# STM32_IO.net
KiCad netlist of a schematic drawn in Altium Designer
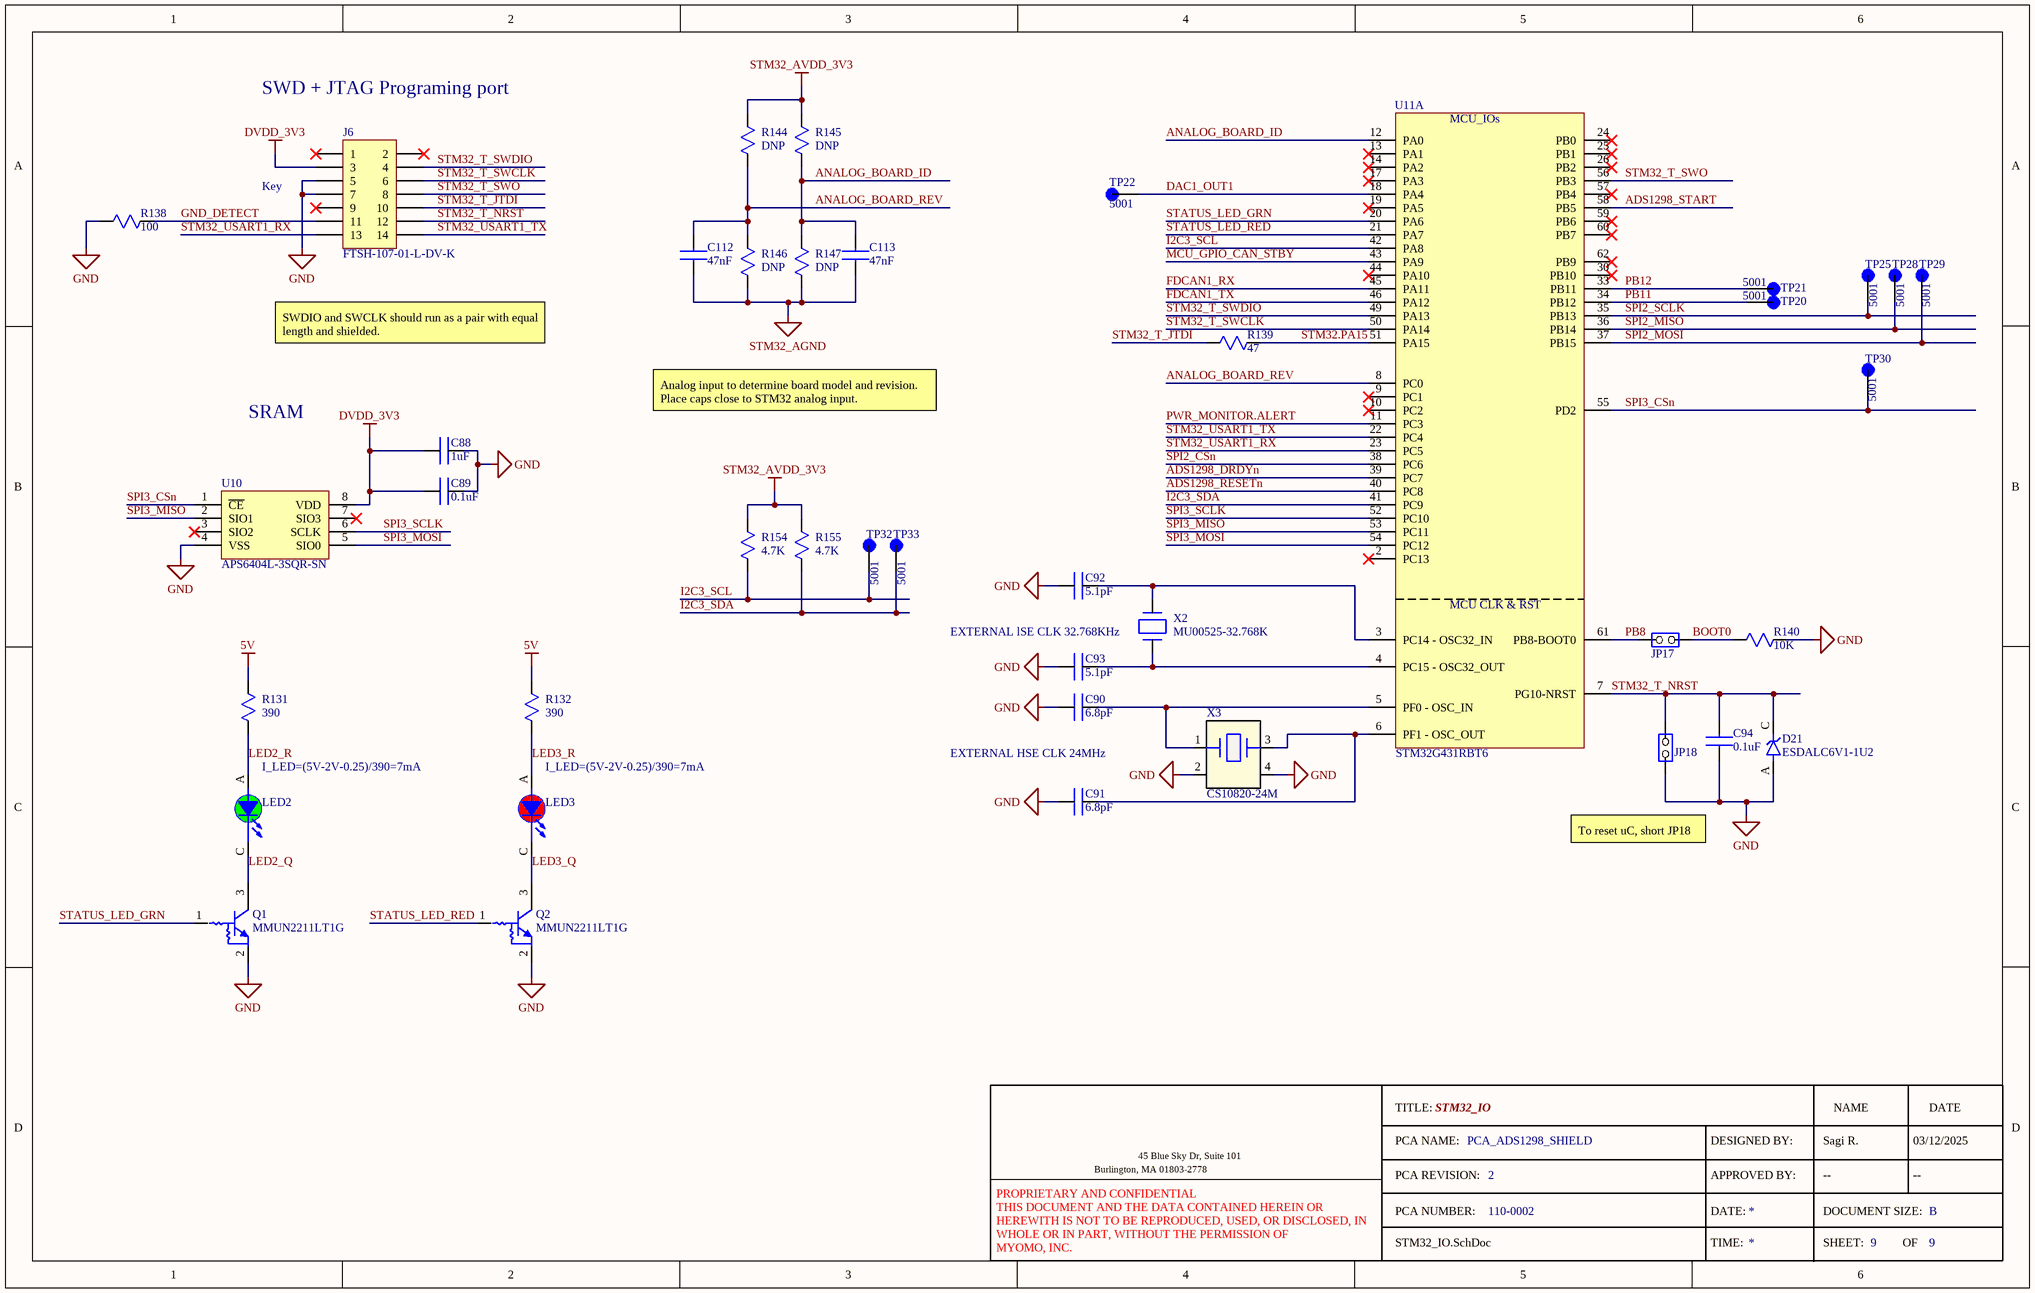
[diagram p0: STM32_IO.SchDoc]

(export (version "E")
  (design (tool "Eeschema 10.0.6"))
  (components
    (comp (ref "C88")
      (value "1uF")
      (footprint "0603")
      (description "CAP CER 1UF 50V X7R 0603")
      (fields (field (name "MFG") "YAGEO"))
      (libsource (lib "Myomo_SCH_Library") (part "C_0603_CER_1uF_50V_X7R"))
    )
    (comp (ref "C89")
      (value "0.1uF")
      (footprint "0402")
      (description "CAP CER 0.1UF 50V X7R 0402")
      (fields (field (name "MFG") "Samsung"))
      (libsource (lib "") (part "C_0402_CER_0.1uF_50V_X7R_1"))
    )
    (comp (ref "C90")
      (value "6.8pF")
      (footprint "0402")
      (description "CAP CER 6.8PF 50V C0G/NPO 0402")
      (fields (field (name "MFG") "YAGEO"))
      (libsource (lib "Myomo_SCH_Library") (part "C_0402_CER_6.8pF_50V_COG"))
    )
    (comp (ref "C91")
      (value "6.8pF")
      (footprint "0402")
      (description "CAP CER 6.8PF 50V C0G/NPO 0402")
      (fields (field (name "MFG") "YAGEO"))
      (libsource (lib "Myomo_SCH_Library") (part "C_0402_CER_6.8pF_50V_COG"))
    )
    (comp (ref "C92")
      (value "5.1pF")
      (footprint "0402")
      (description "CAP CER 5.1PF 50V C0G/NPO 0402")
      (fields (field (name "MFG") "YAGEO"))
      (libsource (lib "Myomo_SCH_Library") (part "C_0402_CER_5.1pF_50V_COG"))
    )
    (comp (ref "C93")
      (value "5.1pF")
      (footprint "0402")
      (description "CAP CER 5.1PF 50V C0G/NPO 0402")
      (fields (field (name "MFG") "YAGEO"))
      (libsource (lib "Myomo_SCH_Library") (part "C_0402_CER_5.1pF_50V_COG"))
    )
    (comp (ref "C94")
      (value "0.1uF")
      (footprint "0402")
      (description "CAP CER 0.1UF 50V X7R 0402")
      (fields (field (name "MFG") "Samsung"))
      (libsource (lib "Myomo_SCH_Library") (part "C_0402_CER_0.1uF_50V_X7R"))
    )
    (comp (ref "C112")
      (value "47nF")
      (footprint "0402")
      (description "CAP CER 47nF 50V X7R 0402")
      (fields (field (name "MFG") "TDK"))
      (libsource (lib "Myomo_SCH_Library") (part "C_0402_CER_47nF_50V_X7R"))
    )
    (comp (ref "C113")
      (value "47nF")
      (footprint "0402")
      (description "CAP CER 47nF 50V X7R 0402")
      (fields (field (name "MFG") "TDK"))
      (libsource (lib "Myomo_SCH_Library") (part "C_0402_CER_47nF_50V_X7R"))
    )
    (comp (ref "D21")
      (value "ESDALC6V1-1U2")
      (footprint "D_TVS_6.1V_20W")
      (description "TVS DIODE 3VRS ST 0201")
      (fields (field (name "MFG") "STMicroelectronics"))
      (libsource (lib "Myomo_SCH_Library") (part "D_TVS_6.1V_20W"))
    )
    (comp (ref "J6")
      (value "FTSH-107-01-L-DV-K")
      (footprint "J_SAMTEC_FTSH-107-01-L-DV-K")
      (description "CONN HEADER SMD 14POS 1.27MM")
      (fields (field (name "MFG") "Samtec"))
      (libsource (lib "Myomo_SCH_Library") (part "J_SAMTEC_FTSH-107-01-L-DV-K"))
    )
    (comp (ref "JP17")
      (value "JP_1x2_TSW-102-07-F-S")
      (footprint "JP_1x2_TSW-102-07-F-S")
      (description "CONN HEADER VERT 2POS 2.54MM")
      (fields (field (name "MFG") "SAMTEC"))
      (libsource (lib "Myomo_SCH_Library") (part "JP_1x2_TSW-102-07-F-S"))
    )
    (comp (ref "JP18")
      (value "JP_1x2_TSW-102-07-F-S")
      (footprint "JP_1x2_TSW-102-07-F-S")
      (description "CONN HEADER VERT 2POS 2.54MM")
      (fields (field (name "MFG") "SAMTEC"))
      (libsource (lib "Myomo_SCH_Library") (part "JP_1x2_TSW-102-07-F-S"))
    )
    (comp (ref "LED2")
      (value "D_LED_GREEN_LTST")
      (footprint "D_LED_GREEN_LTST")
      (description "LED GREEN CLEAR 0603 SMD")
      (fields (field (name "MFG") "Lite-On Inc."))
      (libsource (lib "Myomo_SCH_Library") (part "D_LED_GREEN_LTST"))
    )
    (comp (ref "LED3")
      (value "D_LED_RED_LTST")
      (footprint "D_LED_RED_LTST")
      (description "LED RED CLEAR SMD")
      (fields (field (name "MFG") "Lite-On Inc."))
      (libsource (lib "Myomo_SCH_Library") (part "D_LED_RED_LTST"))
    )
    (comp (ref "Q1")
      (value "MMUN2211LT1G")
      (footprint "Q_NPN_PREBIAS_MMUN2211LT1G")
      (description "TRANS PREBIAS NPN 246MW SOT23-3")
      (fields (field (name "MFG") "ON Semiconductor"))
      (libsource (lib "Myomo_SCH_Library") (part "Q_NPN_PREBIAS_MMUN2211LT1G"))
    )
    (comp (ref "Q2")
      (value "MMUN2211LT1G")
      (footprint "Q_NPN_PREBIAS_MMUN2211LT1G")
      (description "TRANS PREBIAS NPN 246MW SOT23-3")
      (fields (field (name "MFG") "ON Semiconductor"))
      (libsource (lib "Myomo_SCH_Library") (part "Q_NPN_PREBIAS_MMUN2211LT1G"))
    )
    (comp (ref "R131")
      (value "390")
      (footprint "0603")
      (description "RES 390 OHM 1% 1/10W 0603")
      (fields (field (name "MFG") "YAGEO"))
      (libsource (lib "Myomo_SCH_Library") (part "R_0603_390_1%_1/10W"))
    )
    (comp (ref "R132")
      (value "390")
      (footprint "0603")
      (description "RES 390 OHM 1% 1/10W 0603")
      (fields (field (name "MFG") "YAGEO"))
      (libsource (lib "Myomo_SCH_Library") (part "R_0603_390_1%_1/10W"))
    )
    (comp (ref "R138")
      (value "100")
      (footprint "0402")
      (description "RES SMD 100 OHM 1% 1/10W 0402")
      (fields (field (name "MFG") "Panasonic"))
      (libsource (lib "Myomo_SCH_Library") (part "R_0402_100_1%_1/10W"))
    )
    (comp (ref "R139")
      (value "47")
      (footprint "0402")
      (description "RES SMD 47 OHM 1% 1/10W 0402")
      (fields (field (name "MFG") "Panasonic"))
      (libsource (lib "Myomo_SCH_Library") (part "R_0402_47_1%_1/10W"))
    )
    (comp (ref "R140")
      (value "10K")
      (footprint "0402")
      (description "RES SMD 10K OHM 1% 1/10W 0402")
      (fields (field (name "MFG") "Panasonic"))
      (libsource (lib "Myomo_SCH_Library") (part "R_0402_10K_1%_1/10W"))
    )
    (comp (ref "R144")
      (value "DNP")
      (footprint "0603")
      (description "RES 0603 DNP")
      (libsource (lib "Myomo_SCH_Library") (part "R_0603_DNP"))
    )
    (comp (ref "R145")
      (value "DNP")
      (footprint "0603")
      (description "RES 0603 DNP")
      (libsource (lib "Myomo_SCH_Library") (part "R_0603_DNP"))
    )
    (comp (ref "R146")
      (value "DNP")
      (footprint "0603")
      (description "RES 0603 DNP")
      (libsource (lib "Myomo_SCH_Library") (part "R_0603_DNP"))
    )
    (comp (ref "R147")
      (value "DNP")
      (footprint "0603")
      (description "RES 0603 DNP")
      (libsource (lib "Myomo_SCH_Library") (part "R_0603_DNP"))
    )
    (comp (ref "R154")
      (value "4.7K")
      (footprint "0402")
      (description "RES SMD 4.7K OHM 1% 1/10W 0402")
      (fields (field (name "MFG") "Panasonic"))
      (libsource (lib "Myomo_SCH_Library") (part "R_0402_4.7K_1%_1/10W"))
    )
    (comp (ref "R155")
      (value "4.7K")
      (footprint "0402")
      (description "RES SMD 4.7K OHM 1% 1/10W 0402")
      (fields (field (name "MFG") "Panasonic"))
      (libsource (lib "Myomo_SCH_Library") (part "R_0402_4.7K_1%_1/10W"))
    )
    (comp (ref "TP20")
      (value "5001")
      (footprint "TP_CLIP_BLK_5001")
      (description "PC TEST POINT MINIATURE BLACK")
      (fields (field (name "MFG") "Keystone Electronics"))
      (libsource (lib "Myomo_SCH_Library") (part "TP_CLIP_BLK_5001"))
    )
    (comp (ref "TP21")
      (value "5001")
      (footprint "TP_CLIP_BLK_5001")
      (description "PC TEST POINT MINIATURE BLACK")
      (fields (field (name "MFG") "Keystone Electronics"))
      (libsource (lib "Myomo_SCH_Library") (part "TP_CLIP_BLK_5001"))
    )
    (comp (ref "TP22")
      (value "5001")
      (footprint "TP_CLIP_BLK_5001")
      (description "PC TEST POINT MINIATURE BLACK")
      (fields (field (name "MFG") "Keystone Electronics"))
      (libsource (lib "Myomo_SCH_Library") (part "TP_CLIP_BLK_5001"))
    )
    (comp (ref "TP25")
      (value "5001")
      (footprint "TP_CLIP_BLK_5001")
      (description "PC TEST POINT MINIATURE BLACK")
      (fields (field (name "MFG") "Keystone Electronics"))
      (libsource (lib "Myomo_SCH_Library") (part "TP_CLIP_BLK_5001"))
    )
    (comp (ref "TP28")
      (value "5001")
      (footprint "TP_CLIP_BLK_5001")
      (description "PC TEST POINT MINIATURE BLACK")
      (fields (field (name "MFG") "Keystone Electronics"))
      (libsource (lib "Myomo_SCH_Library") (part "TP_CLIP_BLK_5001"))
    )
    (comp (ref "TP29")
      (value "5001")
      (footprint "TP_CLIP_BLK_5001")
      (description "PC TEST POINT MINIATURE BLACK")
      (fields (field (name "MFG") "Keystone Electronics"))
      (libsource (lib "Myomo_SCH_Library") (part "TP_CLIP_BLK_5001"))
    )
    (comp (ref "TP30")
      (value "5001")
      (footprint "TP_CLIP_BLK_5001")
      (description "PC TEST POINT MINIATURE BLACK")
      (fields (field (name "MFG") "Keystone Electronics"))
      (libsource (lib "Myomo_SCH_Library") (part "TP_CLIP_BLK_5001"))
    )
    (comp (ref "TP32")
      (value "5001")
      (footprint "TP_CLIP_BLK_5001")
      (description "PC TEST POINT MINIATURE BLACK")
      (fields (field (name "MFG") "Keystone Electronics"))
      (libsource (lib "Myomo_SCH_Library") (part "TP_CLIP_BLK_5001"))
    )
    (comp (ref "TP33")
      (value "5001")
      (footprint "TP_CLIP_BLK_5001")
      (description "PC TEST POINT MINIATURE BLACK")
      (fields (field (name "MFG") "Keystone Electronics"))
      (libsource (lib "Myomo_SCH_Library") (part "TP_CLIP_BLK_5001"))
    )
    (comp (ref "U10")
      (value "APS6404L-3SQR-SN")
      (footprint "U_APS6404L-3SQR-SN")
      (description "DRAM IoT RAM 64Mb QSPI (x1,x4) SDR 133/84MHz, RBX, 3V, Ind. Temp., SOP8")
      (fields (field (name "MFG") "AP Memory"))
      (libsource (lib "Myomo_SCH_Library") (part "U_APS6404L-3SQR-SN"))
    )
    (comp (ref "U11")
      (value "STM32G431RBT6")
      (footprint "U_STM32G431R")
      (description "STM32G431, LQFP64 package")
      (fields (field (name "MFG") "STMicroelectronics"))
      (libsource (lib "Myomo_SCH_Library") (part "U_STM32G431R"))
    )
    (comp (ref "X2")
      (value "MU00525-32.768K")
      (footprint "XTAL_32.768KHZ_20PPM")
      (description "XTAL OSC 32.7680KHZ 6PF SMD")
      (fields (field (name "MFG") "NDK"))
      (libsource (lib "Myomo_SCH_Library") (part "XTAL_32.768KHZ_20PPM"))
    )
    (comp (ref "X3")
      (value "CS10820-24M")
      (footprint "XTAL_24.0000MHZ_15PPM")
      (description "XTAL OSC 24 MHz ±15ppm Crystal 6pF 80 Ohms 4-SMD, No Lead")
      (fields (field (name "MFG") "NDK"))
      (libsource (lib "Myomo_SCH_Library") (part "XTAL_24.0000MHZ_15PPM"))
    )
  )
  (nets
    (net (code "1") (name "/ADS1298_DRDYn") (class "Default")
      (node (ref "U11") (pin "39") (pinfunction "PC7_39") (pintype "passive"))
    )
    (net (code "2") (name "/ADS1298_RESETn") (class "Default")
      (node (ref "U11") (pin "40") (pinfunction "PC8_40") (pintype "passive"))
    )
    (net (code "3") (name "/ADS1298_START") (class "Default")
      (node (ref "U11") (pin "58") (pinfunction "PB5_58") (pintype "passive"))
    )
    (net (code "4") (name "/ANALOG_BOARD_ID") (class "Default")
      (node (ref "C113") (pin "1") (pinfunction "1_1") (pintype "passive"))
      (node (ref "R145") (pin "2") (pinfunction "2_2") (pintype "passive"))
      (node (ref "R147") (pin "1") (pinfunction "1_1") (pintype "passive"))
      (node (ref "U11") (pin "12") (pinfunction "PA0_12") (pintype "passive"))
    )
    (net (code "5") (name "/ANALOG_BOARD_REV") (class "Default")
      (node (ref "C112") (pin "1") (pinfunction "1_1") (pintype "passive"))
      (node (ref "R144") (pin "2") (pinfunction "2_2") (pintype "passive"))
      (node (ref "R146") (pin "1") (pinfunction "1_1") (pintype "passive"))
      (node (ref "U11") (pin "8") (pinfunction "PC0_8") (pintype "passive"))
    )
    (net (code "6") (name "/BOOT0") (class "Default")
      (node (ref "JP17") (pin "2") (pinfunction "2_2") (pintype "passive"))
      (node (ref "R140") (pin "1") (pinfunction "1_1") (pintype "passive"))
    )
    (net (code "7") (name "/DAC1_OUT1") (class "Default")
      (node (ref "TP22") (pin "TP") (pinfunction "TP_TP") (pintype "passive"))
      (node (ref "U11") (pin "18") (pinfunction "PA4_18") (pintype "passive"))
    )
    (net (code "8") (name "/FDCAN1_RX") (class "Default")
      (node (ref "U11") (pin "45") (pinfunction "PA11_45") (pintype "passive"))
    )
    (net (code "9") (name "/FDCAN1_TX") (class "Default")
      (node (ref "U11") (pin "46") (pinfunction "PA12_46") (pintype "passive"))
    )
    (net (code "10") (name "/GND_DETECT") (class "Default")
      (node (ref "J6") (pin "11") (pinfunction "11_11") (pintype "passive"))
      (node (ref "R138") (pin "2") (pinfunction "2_2") (pintype "passive"))
    )
    (net (code "11") (name "/I2C3_SCL") (class "Default")
      (node (ref "R154") (pin "2") (pinfunction "2_2") (pintype "passive"))
      (node (ref "TP32") (pin "TP") (pinfunction "TP_TP") (pintype "passive"))
      (node (ref "U11") (pin "42") (pinfunction "PA8_42") (pintype "passive"))
    )
    (net (code "12") (name "/I2C3_SDA") (class "Default")
      (node (ref "R155") (pin "2") (pinfunction "2_2") (pintype "passive"))
      (node (ref "TP33") (pin "TP") (pinfunction "TP_TP") (pintype "passive"))
      (node (ref "U11") (pin "41") (pinfunction "PC9_41") (pintype "passive"))
    )
    (net (code "13") (name "/LED2_Q") (class "Default")
      (node (ref "LED2") (pin "C") (pinfunction "CATHODE_C") (pintype "passive"))
      (node (ref "Q1") (pin "3") (pinfunction "C_3") (pintype "passive"))
    )
    (net (code "14") (name "/LED2_R") (class "Default")
      (node (ref "LED2") (pin "A") (pinfunction "ANODE_A") (pintype "passive"))
      (node (ref "R131") (pin "2") (pinfunction "2_2") (pintype "passive"))
    )
    (net (code "15") (name "/LED3_Q") (class "Default")
      (node (ref "LED3") (pin "C") (pinfunction "CATHODE_C") (pintype "passive"))
      (node (ref "Q2") (pin "3") (pinfunction "C_3") (pintype "passive"))
    )
    (net (code "16") (name "/LED3_R") (class "Default")
      (node (ref "LED3") (pin "A") (pinfunction "ANODE_A") (pintype "passive"))
      (node (ref "R132") (pin "2") (pinfunction "2_2") (pintype "passive"))
    )
    (net (code "17") (name "/MCU_GPIO_CAN_STBY") (class "Default")
      (node (ref "U11") (pin "43") (pinfunction "PA9_43") (pintype "passive"))
    )
    (net (code "18") (name "/PB8") (class "Default")
      (node (ref "JP17") (pin "1") (pinfunction "1_1") (pintype "passive"))
      (node (ref "U11") (pin "61") (pinfunction "PB8-BOOT0_61") (pintype "passive"))
    )
    (net (code "19") (name "/PB11") (class "Default")
      (node (ref "TP20") (pin "TP") (pinfunction "TP_TP") (pintype "passive"))
      (node (ref "U11") (pin "34") (pinfunction "PB12_34") (pintype "passive"))
    )
    (net (code "20") (name "/PB12") (class "Default")
      (node (ref "TP21") (pin "TP") (pinfunction "TP_TP") (pintype "passive"))
      (node (ref "U11") (pin "33") (pinfunction "PB11_33") (pintype "passive"))
    )
    (net (code "21") (name "/PWR_MONITOR.ALERT") (class "Default")
      (node (ref "U11") (pin "11") (pinfunction "PC3_11") (pintype "passive"))
    )
    (net (code "22") (name "/SPI2_CSn") (class "Default")
      (node (ref "U11") (pin "38") (pinfunction "PC6_38") (pintype "passive"))
    )
    (net (code "23") (name "/SPI2_MISO") (class "Default")
      (node (ref "TP28") (pin "TP") (pinfunction "TP_TP") (pintype "passive"))
      (node (ref "U11") (pin "36") (pinfunction "PB14_36") (pintype "passive"))
    )
    (net (code "24") (name "/SPI2_MOSI") (class "Default")
      (node (ref "TP29") (pin "TP") (pinfunction "TP_TP") (pintype "passive"))
      (node (ref "U11") (pin "37") (pinfunction "PB15_37") (pintype "passive"))
    )
    (net (code "25") (name "/SPI2_SCLK") (class "Default")
      (node (ref "TP25") (pin "TP") (pinfunction "TP_TP") (pintype "passive"))
      (node (ref "U11") (pin "35") (pinfunction "PB13_35") (pintype "passive"))
    )
    (net (code "26") (name "/SPI3_CSn") (class "Default")
      (node (ref "TP30") (pin "TP") (pinfunction "TP_TP") (pintype "passive"))
      (node (ref "U10") (pin "1") (pinfunction "~{CE}_1") (pintype "power_in"))
      (node (ref "U11") (pin "55") (pinfunction "PD2_55") (pintype "passive"))
    )
    (net (code "27") (name "/SPI3_MISO") (class "Default")
      (node (ref "U10") (pin "2") (pinfunction "SIO1_2") (pintype "power_in"))
      (node (ref "U11") (pin "53") (pinfunction "PC11_53") (pintype "passive"))
    )
    (net (code "28") (name "/SPI3_MOSI") (class "Default")
      (node (ref "U10") (pin "5") (pinfunction "SIO0_5") (pintype "power_in"))
      (node (ref "U11") (pin "54") (pinfunction "PC12_54") (pintype "passive"))
    )
    (net (code "29") (name "/SPI3_SCLK") (class "Default")
      (node (ref "U10") (pin "6") (pinfunction "SCLK_6") (pintype "power_in"))
      (node (ref "U11") (pin "52") (pinfunction "PC10_52") (pintype "passive"))
    )
    (net (code "30") (name "/STATUS_LED_GRN") (class "Default")
      (node (ref "Q1") (pin "1") (pinfunction "B_1") (pintype "passive"))
      (node (ref "U11") (pin "20") (pinfunction "PA6_20") (pintype "passive"))
    )
    (net (code "31") (name "/STATUS_LED_RED") (class "Default")
      (node (ref "Q2") (pin "1") (pinfunction "B_1") (pintype "passive"))
      (node (ref "U11") (pin "21") (pinfunction "PA7_21") (pintype "passive"))
    )
    (net (code "32") (name "/STM32.PA15") (class "Default")
      (node (ref "R139") (pin "2") (pinfunction "2_2") (pintype "passive"))
      (node (ref "U11") (pin "51") (pinfunction "PA15_51") (pintype "passive"))
    )
    (net (code "33") (name "/STM32_T_JTDI") (class "Default")
      (node (ref "J6") (pin "10") (pinfunction "10_10") (pintype "passive"))
      (node (ref "R139") (pin "1") (pinfunction "1_1") (pintype "passive"))
    )
    (net (code "34") (name "/STM32_T_NRST") (class "Default")
      (node (ref "C94") (pin "1") (pinfunction "1_1") (pintype "passive"))
      (node (ref "D21") (pin "C") (pinfunction "C_C") (pintype "passive"))
      (node (ref "J6") (pin "12") (pinfunction "12_12") (pintype "passive"))
      (node (ref "JP18") (pin "2") (pinfunction "2_2") (pintype "passive"))
      (node (ref "U11") (pin "7") (pinfunction "PG10-NRST_7") (pintype "passive"))
    )
    (net (code "35") (name "/STM32_T_SWCLK") (class "Default")
      (node (ref "J6") (pin "6") (pinfunction "6_6") (pintype "passive"))
      (node (ref "U11") (pin "50") (pinfunction "PA14_50") (pintype "passive"))
    )
    (net (code "36") (name "/STM32_T_SWDIO") (class "Default")
      (node (ref "J6") (pin "4") (pinfunction "4_4") (pintype "passive"))
      (node (ref "U11") (pin "49") (pinfunction "PA13_49") (pintype "passive"))
    )
    (net (code "37") (name "/STM32_T_SWO") (class "Default")
      (node (ref "J6") (pin "8") (pinfunction "8_8") (pintype "passive"))
      (node (ref "U11") (pin "56") (pinfunction "PB3_56") (pintype "passive"))
    )
    (net (code "38") (name "/STM32_USART1_RX") (class "Default")
      (node (ref "J6") (pin "13") (pinfunction "13_13") (pintype "passive"))
      (node (ref "U11") (pin "23") (pinfunction "PC5_23") (pintype "passive"))
    )
    (net (code "39") (name "/STM32_USART1_TX") (class "Default")
      (node (ref "J6") (pin "14") (pinfunction "14_14") (pintype "passive"))
      (node (ref "U11") (pin "22") (pinfunction "PC4_22") (pintype "passive"))
    )
    (net (code "40") (name "5V") (class "Default")
      (node (ref "R131") (pin "1") (pinfunction "1_1") (pintype "passive"))
      (node (ref "R132") (pin "1") (pinfunction "1_1") (pintype "passive"))
    )
    (net (code "41") (name "DVDD_3V3") (class "Default")
      (node (ref "C88") (pin "1") (pinfunction "1_1") (pintype "passive"))
      (node (ref "C89") (pin "1") (pinfunction "1_1") (pintype "passive"))
      (node (ref "J6") (pin "3") (pinfunction "3_3") (pintype "passive"))
      (node (ref "U10") (pin "8") (pinfunction "VDD_8") (pintype "power_in"))
    )
    (net (code "42") (name "GND") (class "Default")
      (node (ref "C88") (pin "2") (pinfunction "2_2") (pintype "passive"))
      (node (ref "C89") (pin "2") (pinfunction "2_2") (pintype "passive"))
      (node (ref "C90") (pin "1") (pinfunction "1_1") (pintype "passive"))
      (node (ref "C91") (pin "1") (pinfunction "1_1") (pintype "passive"))
      (node (ref "C92") (pin "1") (pinfunction "1_1") (pintype "passive"))
      (node (ref "C93") (pin "1") (pinfunction "1_1") (pintype "passive"))
      (node (ref "C94") (pin "2") (pinfunction "2_2") (pintype "passive"))
      (node (ref "D21") (pin "A") (pinfunction "A_A") (pintype "passive"))
      (node (ref "J6") (pin "5") (pinfunction "5_5") (pintype "passive"))
      (node (ref "J6") (pin "7") (pinfunction "7_7") (pintype "passive"))
      (node (ref "JP18") (pin "1") (pinfunction "1_1") (pintype "passive"))
      (node (ref "Q1") (pin "2") (pinfunction "E_2") (pintype "passive"))
      (node (ref "Q2") (pin "2") (pinfunction "E_2") (pintype "passive"))
      (node (ref "R138") (pin "1") (pinfunction "1_1") (pintype "passive"))
      (node (ref "R140") (pin "2") (pinfunction "2_2") (pintype "passive"))
      (node (ref "U10") (pin "4") (pinfunction "VSS_4") (pintype "power_in"))
      (node (ref "X3") (pin "2") (pinfunction "X2_2") (pintype "passive"))
      (node (ref "X3") (pin "4") (pinfunction "X4_4") (pintype "passive"))
    )
    (net (code "43") (name "Net-(U11A-PC14_-_OSC32_IN)") (class "Default")
      (node (ref "C92") (pin "2") (pinfunction "2_2") (pintype "passive"))
      (node (ref "U11") (pin "3") (pinfunction "PC14_-_OSC32_IN_3") (pintype "passive"))
      (node (ref "X2") (pin "1") (pinfunction "X1_1") (pintype "passive"))
    )
    (net (code "44") (name "Net-(U11A-PC15_-_OSC32_OUT)") (class "Default")
      (node (ref "C93") (pin "2") (pinfunction "2_2") (pintype "passive"))
      (node (ref "U11") (pin "4") (pinfunction "PC15_-_OSC32_OUT_4") (pintype "passive"))
      (node (ref "X2") (pin "2") (pinfunction "X2_2") (pintype "passive"))
    )
    (net (code "45") (name "Net-(U11A-PF0_-_OSC_IN)") (class "Default")
      (node (ref "C90") (pin "2") (pinfunction "2_2") (pintype "passive"))
      (node (ref "U11") (pin "5") (pinfunction "PF0_-_OSC_IN_5") (pintype "passive"))
      (node (ref "X3") (pin "1") (pinfunction "X1_1") (pintype "passive"))
    )
    (net (code "46") (name "Net-(U11A-PF1_-_OSC_OUT)") (class "Default")
      (node (ref "C91") (pin "2") (pinfunction "2_2") (pintype "passive"))
      (node (ref "U11") (pin "6") (pinfunction "PF1_-_OSC_OUT_6") (pintype "passive"))
      (node (ref "X3") (pin "3") (pinfunction "X3_3") (pintype "passive"))
    )
    (net (code "47") (name "STM32_AGND") (class "Default")
      (node (ref "C112") (pin "2") (pinfunction "2_2") (pintype "passive"))
      (node (ref "C113") (pin "2") (pinfunction "2_2") (pintype "passive"))
      (node (ref "R146") (pin "2") (pinfunction "2_2") (pintype "passive"))
      (node (ref "R147") (pin "2") (pinfunction "2_2") (pintype "passive"))
    )
    (net (code "48") (name "STM32_AVDD_3V3") (class "Default")
      (node (ref "R144") (pin "1") (pinfunction "1_1") (pintype "passive"))
      (node (ref "R145") (pin "1") (pinfunction "1_1") (pintype "passive"))
      (node (ref "R154") (pin "1") (pinfunction "1_1") (pintype "passive"))
      (node (ref "R155") (pin "1") (pinfunction "1_1") (pintype "passive"))
    )
    (net (code "49") (name "unconnected-(J6-Pad1)") (class "Default")
      (node (ref "J6") (pin "1") (pinfunction "1_1") (pintype "passive+no_connect"))
    )
    (net (code "50") (name "unconnected-(J6-Pad2)") (class "Default")
      (node (ref "J6") (pin "2") (pinfunction "2_2") (pintype "passive+no_connect"))
    )
    (net (code "51") (name "unconnected-(J6-Pad9)") (class "Default")
      (node (ref "J6") (pin "9") (pinfunction "9_9") (pintype "passive+no_connect"))
    )
    (net (code "52") (name "unconnected-(U10-SIO2-Pad3)") (class "Default")
      (node (ref "U10") (pin "3") (pinfunction "SIO2_3") (pintype "power_in+no_connect"))
    )
    (net (code "53") (name "unconnected-(U10-SIO3-Pad7)") (class "Default")
      (node (ref "U10") (pin "7") (pinfunction "SIO3_7") (pintype "power_in+no_connect"))
    )
    (net (code "54") (name "unconnected-(U11A-PA1-Pad13)") (class "Default")
      (node (ref "U11") (pin "13") (pinfunction "PA1_13") (pintype "passive+no_connect"))
    )
    (net (code "55") (name "unconnected-(U11A-PA2-Pad14)") (class "Default")
      (node (ref "U11") (pin "14") (pinfunction "PA2_14") (pintype "passive+no_connect"))
    )
    (net (code "56") (name "unconnected-(U11A-PA3-Pad17)") (class "Default")
      (node (ref "U11") (pin "17") (pinfunction "PA3_17") (pintype "passive+no_connect"))
    )
    (net (code "57") (name "unconnected-(U11A-PA5-Pad19)") (class "Default")
      (node (ref "U11") (pin "19") (pinfunction "PA5_19") (pintype "passive+no_connect"))
    )
    (net (code "58") (name "unconnected-(U11A-PA10-Pad44)") (class "Default")
      (node (ref "U11") (pin "44") (pinfunction "PA10_44") (pintype "passive+no_connect"))
    )
    (net (code "59") (name "unconnected-(U11A-PB0-Pad24)") (class "Default")
      (node (ref "U11") (pin "24") (pinfunction "PB0_24") (pintype "passive+no_connect"))
    )
    (net (code "60") (name "unconnected-(U11A-PB1-Pad25)") (class "Default")
      (node (ref "U11") (pin "25") (pinfunction "PB1_25") (pintype "passive+no_connect"))
    )
    (net (code "61") (name "unconnected-(U11A-PB2-Pad26)") (class "Default")
      (node (ref "U11") (pin "26") (pinfunction "PB2_26") (pintype "passive+no_connect"))
    )
    (net (code "62") (name "unconnected-(U11A-PB4-Pad57)") (class "Default")
      (node (ref "U11") (pin "57") (pinfunction "PB4_57") (pintype "passive+no_connect"))
    )
    (net (code "63") (name "unconnected-(U11A-PB6-Pad59)") (class "Default")
      (node (ref "U11") (pin "59") (pinfunction "PB6_59") (pintype "passive+no_connect"))
    )
    (net (code "64") (name "unconnected-(U11A-PB7-Pad60)") (class "Default")
      (node (ref "U11") (pin "60") (pinfunction "PB7_60") (pintype "passive+no_connect"))
    )
    (net (code "65") (name "unconnected-(U11A-PB9-Pad62)") (class "Default")
      (node (ref "U11") (pin "62") (pinfunction "PB9_62") (pintype "passive+no_connect"))
    )
    (net (code "66") (name "unconnected-(U11A-PB10-Pad30)") (class "Default")
      (node (ref "U11") (pin "30") (pinfunction "PB10_30") (pintype "passive+no_connect"))
    )
    (net (code "67") (name "unconnected-(U11A-PC1-Pad9)") (class "Default")
      (node (ref "U11") (pin "9") (pinfunction "PC1_9") (pintype "passive+no_connect"))
    )
    (net (code "68") (name "unconnected-(U11A-PC2-Pad10)") (class "Default")
      (node (ref "U11") (pin "10") (pinfunction "PC2_10") (pintype "passive+no_connect"))
    )
    (net (code "69") (name "unconnected-(U11A-PC13-Pad2)") (class "Default")
      (node (ref "U11") (pin "2") (pinfunction "PC13_2") (pintype "passive+no_connect"))
    )
  )
)
